# 24V_to_5V.net
KiCad netlist of a schematic drawn in Altium Designer
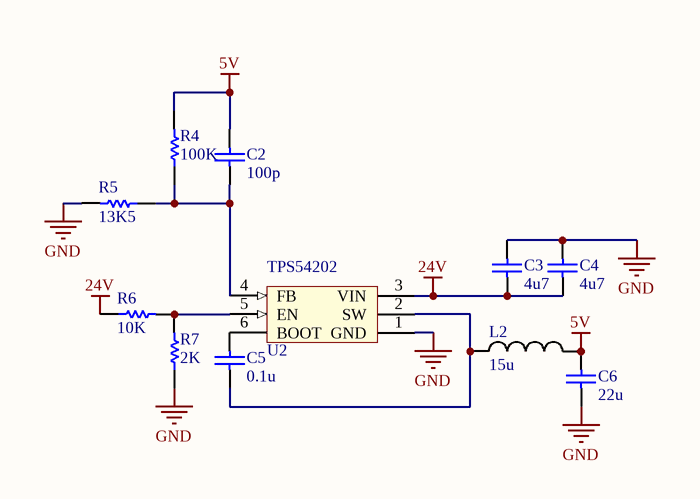
[diagram p0: 24V_to_5V.SchDoc]

(export (version "E")
  (design (tool "Eeschema 10.0.6"))
  (components
    (comp (ref "C2")
      (value "100p")
      (footprint "CAPC1608X90N")
      (description "Capacitor")
      (fields (field (name "Comment") "Cap") (field (name "PUBLISHER") "Altium Limited"))
      (libsource (lib "IOBoard_Low") (part "Cap"))
    )
    (comp (ref "C3")
      (value "4u7")
      (footprint "CAPC2012X135N")
      (description "Capacitor")
      (fields (field (name "Comment") "Cap") (field (name "PUBLISHER") "Altium Limited"))
      (libsource (lib "IOBoard_Low") (part "Cap"))
    )
    (comp (ref "C4")
      (value "4u7")
      (footprint "CAPC2012X135N")
      (description "Capacitor")
      (fields (field (name "Comment") "Cap") (field (name "PUBLISHER") "Altium Limited"))
      (libsource (lib "IOBoard_Low") (part "Cap"))
    )
    (comp (ref "C5")
      (value "0.1u")
      (footprint "CAPC1608X90N")
      (description "Capacitor")
      (fields (field (name "Comment") "Cap") (field (name "PUBLISHER") "Altium Limited"))
      (libsource (lib "IOBoard_Low") (part "Cap"))
    )
    (comp (ref "C6")
      (value "22u")
      (footprint "CAPC2012X135N")
      (description "Capacitor")
      (fields (field (name "Comment") "Cap") (field (name "PUBLISHER") "Altium Limited"))
      (libsource (lib "IOBoard_Low") (part "Cap"))
    )
    (comp (ref "L2")
      (value "15u")
      (footprint "INDC_5.5x5.3x3")
      (description "15uH inductor with 2A saturation current. Dimension is 5.5 * 5.2 * 3 mm^3")
      (fields (field (name "Comment") "15uH inductor"))
      (libsource (lib "IOBoard_Low") (part "INDC_MPX1D0530L150"))
    )
    (comp (ref "R4")
      (value "100K")
      (footprint "RESC1608X55N")
      (description "Resistor")
      (fields (field (name "Comment") "Res1") (field (name "PUBLISHER") "Altium Limited"))
      (libsource (lib "IOBoard_Low") (part "Res1"))
    )
    (comp (ref "R5")
      (value "13K5")
      (footprint "RESC1608X55N")
      (description "Resistor")
      (fields (field (name "Comment") "Res1") (field (name "PUBLISHER") "Altium Limited"))
      (libsource (lib "IOBoard_Low") (part "Res1"))
    )
    (comp (ref "R6")
      (value "10K")
      (footprint "RESC1608X55N")
      (description "Resistor")
      (fields (field (name "Comment") "Res1") (field (name "PUBLISHER") "Altium Limited"))
      (libsource (lib "IOBoard_Low") (part "Res1"))
    )
    (comp (ref "R7")
      (value "2K")
      (footprint "RESC1608X55N")
      (description "Resistor")
      (fields (field (name "Comment") "Res1") (field (name "PUBLISHER") "Altium Limited"))
      (libsource (lib "IOBoard_Low") (part "Res1"))
    )
    (comp (ref "U2")
      (value "TPS54202")
      (footprint "SOT23-6")
      (description "4.5-28V input 2A output step down, EMI Friendly Synchronous Step Down Converter")
      (libsource (lib "IOBoard_Low") (part "TPS54202"))
    )
  )
  (nets
    (net (code "1") (name "5V") (class "Default")
      (node (ref "C2") (pin "2") (pinfunction "2_2") (pintype "passive"))
      (node (ref "C6") (pin "2") (pinfunction "2_2") (pintype "passive"))
      (node (ref "L2") (pin "2") (pinfunction "2_2") (pintype "passive"))
      (node (ref "R4") (pin "2") (pinfunction "2_2") (pintype "passive"))
    )
    (net (code "2") (name "24V") (class "Default")
      (node (ref "C3") (pin "2") (pinfunction "2_2") (pintype "passive"))
      (node (ref "C4") (pin "2") (pinfunction "2_2") (pintype "passive"))
      (node (ref "R6") (pin "1") (pinfunction "1_1") (pintype "passive"))
      (node (ref "U2") (pin "3") (pinfunction "VIN_3") (pintype "power_in"))
    )
    (net (code "3") (name "GND") (class "Default")
      (node (ref "C3") (pin "1") (pinfunction "1_1") (pintype "passive"))
      (node (ref "C4") (pin "1") (pinfunction "1_1") (pintype "passive"))
      (node (ref "C6") (pin "1") (pinfunction "1_1") (pintype "passive"))
      (node (ref "R5") (pin "2") (pinfunction "2_2") (pintype "passive"))
      (node (ref "R7") (pin "1") (pinfunction "1_1") (pintype "passive"))
      (node (ref "U2") (pin "1") (pinfunction "GND_1") (pintype "power_in"))
    )
    (net (code "4") (name "Net-(U2-BOOT)") (class "Default")
      (node (ref "C5") (pin "2") (pinfunction "2_2") (pintype "passive"))
      (node (ref "U2") (pin "6") (pinfunction "BOOT_6") (pintype "passive"))
    )
    (net (code "5") (name "Net-(U2-EN)") (class "Default")
      (node (ref "R6") (pin "2") (pinfunction "2_2") (pintype "passive"))
      (node (ref "R7") (pin "2") (pinfunction "2_2") (pintype "passive"))
      (node (ref "U2") (pin "5") (pinfunction "EN_5") (pintype "input"))
    )
    (net (code "6") (name "Net-(U2-FB)") (class "Default")
      (node (ref "C2") (pin "1") (pinfunction "1_1") (pintype "passive"))
      (node (ref "R4") (pin "1") (pinfunction "1_1") (pintype "passive"))
      (node (ref "R5") (pin "1") (pinfunction "1_1") (pintype "passive"))
      (node (ref "U2") (pin "4") (pinfunction "FB_4") (pintype "input"))
    )
    (net (code "7") (name "Net-(U2-SW)") (class "Default")
      (node (ref "C5") (pin "1") (pinfunction "1_1") (pintype "passive"))
      (node (ref "L2") (pin "1") (pinfunction "1_1") (pintype "passive"))
      (node (ref "U2") (pin "2") (pinfunction "SW_2") (pintype "power_in"))
    )
  )
)
